# NJM2670.net
KiCad netlist of a schematic drawn in EAGLE
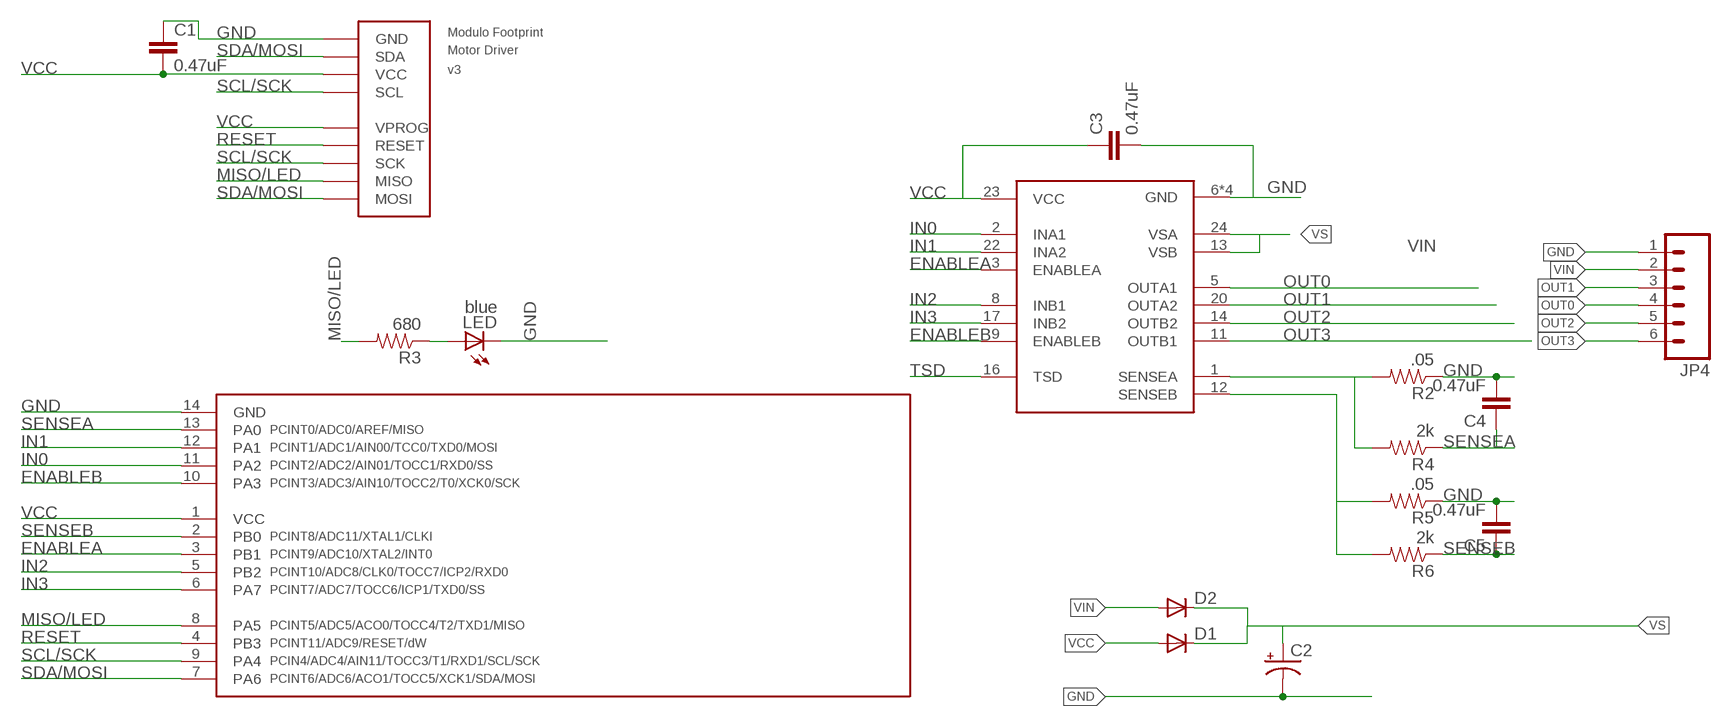
[diagram p0: schematic, sheet 1]

(export (version "E")
  (design (tool "Eeschema 10.0.6"))
  (components
    (comp (ref "C1")
      (value "0.47uF")
      (footprint "eagle-import:0805")
      (libsource (lib "eagle-import") (part "CAP0805"))
    )
    (comp (ref "C2")
      (value "CAP_POLC")
      (footprint "eagle-import:PANASONIC_C")
      (libsource (lib "eagle-import") (part "CAP_POLC"))
    )
    (comp (ref "C3")
      (value "0.47uF")
      (footprint "eagle-import:0805")
      (libsource (lib "eagle-import") (part "CAP0805"))
    )
    (comp (ref "C4")
      (value "0.47uF")
      (footprint "eagle-import:0805")
      (libsource (lib "eagle-import") (part "CAP0805"))
    )
    (comp (ref "C5")
      (value "0.47uF")
      (footprint "eagle-import:0805")
      (libsource (lib "eagle-import") (part "CAP0805"))
    )
    (comp (ref "D1")
      (value "DIODESMA")
      (footprint "eagle-import:SMA-DIODE")
      (libsource (lib "eagle-import") (part "DIODESMA"))
    )
    (comp (ref "D2")
      (value "DIODESMA")
      (footprint "eagle-import:SMA-DIODE")
      (libsource (lib "eagle-import") (part "DIODESMA"))
    )
    (comp (ref "JP4")
      (value "M063.5MM-6")
      (footprint "eagle-import:SCREWTERMINAL-3.5MM-6")
      (libsource (lib "eagle-import") (part "M063.5MM-6"))
    )
    (comp (ref "LED")
      (value "blue")
      (footprint "eagle-import:CHIPLED_0805")
      (libsource (lib "eagle-import") (part "LEDCHIPLED_0805"))
    )
    (comp (ref "R2")
      (value ".05")
      (footprint "eagle-import:0805")
      (libsource (lib "eagle-import") (part "RESISTOR0805-RES"))
    )
    (comp (ref "R3")
      (value "680")
      (footprint "eagle-import:0805")
      (libsource (lib "eagle-import") (part "RESISTOR0805-RES"))
    )
    (comp (ref "R4")
      (value "2k")
      (footprint "eagle-import:0805")
      (libsource (lib "eagle-import") (part "RESISTOR0805-RES"))
    )
    (comp (ref "R5")
      (value ".05")
      (footprint "eagle-import:0805")
      (libsource (lib "eagle-import") (part "RESISTOR0805-RES"))
    )
    (comp (ref "R6")
      (value "2k")
      (footprint "eagle-import:0805")
      (libsource (lib "eagle-import") (part "RESISTOR0805-RES"))
    )
    (comp (ref "U$1")
      (value "FOOTPRINTFOOTPRINT-2")
      (footprint "eagle-import:FOOTPRINT2")
      (fields (field (name "BOARD") "Motor Driver") (field (name "VERSION") "v3"))
      (libsource (lib "eagle-import") (part "FOOTPRINTFOOTPRINT-2"))
    )
    (comp (ref "U$3")
      (value "TINY841")
      (footprint "eagle-import:SOIC14")
      (libsource (lib "eagle-import") (part "TINY841"))
    )
    (comp (ref "U$6")
      (value "NJM2670")
      (footprint "eagle-import:SOP-24-E3")
      (libsource (lib "eagle-import") (part "NJM2670"))
    )
  )
  (nets
    (net (code "1") (name "/ENABLEA") (class "Default")
      (node (ref "U$3") (pin "3") (pinfunction "PB1_3") (pintype "bidirectional"))
      (node (ref "U$6") (pin "3") (pinfunction "ENABLEA_3") (pintype "bidirectional"))
    )
    (net (code "2") (name "/ENABLEB") (class "Default")
      (node (ref "U$3") (pin "10") (pinfunction "PA3_10") (pintype "bidirectional"))
      (node (ref "U$6") (pin "9") (pinfunction "ENABLEB_9") (pintype "bidirectional"))
    )
    (net (code "3") (name "/IN0") (class "Default")
      (node (ref "U$3") (pin "11") (pinfunction "PA2_11") (pintype "bidirectional"))
      (node (ref "U$6") (pin "2") (pinfunction "INA1_2") (pintype "bidirectional"))
    )
    (net (code "4") (name "/IN1") (class "Default")
      (node (ref "U$3") (pin "12") (pinfunction "PA1_12") (pintype "bidirectional"))
      (node (ref "U$6") (pin "22") (pinfunction "INA2_22") (pintype "bidirectional"))
    )
    (net (code "5") (name "/IN2") (class "Default")
      (node (ref "U$3") (pin "5") (pinfunction "PB2_5") (pintype "bidirectional"))
      (node (ref "U$6") (pin "8") (pinfunction "INB1_8") (pintype "bidirectional"))
    )
    (net (code "6") (name "/IN3") (class "Default")
      (node (ref "U$3") (pin "6") (pinfunction "PA7_6") (pintype "bidirectional"))
      (node (ref "U$6") (pin "17") (pinfunction "INB2_17") (pintype "bidirectional"))
    )
    (net (code "7") (name "/MISO{slash}LED") (class "Default")
      (node (ref "R3") (pin "2") (pinfunction "2_2") (pintype "passive"))
      (node (ref "U$1") (pin "PROG3") (pinfunction "MISO_PROG3") (pintype "bidirectional"))
      (node (ref "U$3") (pin "8") (pinfunction "PA5_8") (pintype "bidirectional"))
    )
    (net (code "8") (name "/RESET") (class "Default")
      (node (ref "U$1") (pin "PROG1") (pinfunction "RESET_PROG1") (pintype "bidirectional"))
      (node (ref "U$3") (pin "4") (pinfunction "PB3_4") (pintype "bidirectional"))
    )
    (net (code "9") (name "/SCL{slash}SCK") (class "Default")
      (node (ref "U$1") (pin "BUS3") (pinfunction "SCL_BUS3") (pintype "bidirectional"))
      (node (ref "U$1") (pin "PROG2") (pinfunction "SCK_PROG2") (pintype "bidirectional"))
      (node (ref "U$3") (pin "9") (pinfunction "PA4_9") (pintype "bidirectional"))
    )
    (net (code "10") (name "/SDA{slash}MOSI") (class "Default")
      (node (ref "U$1") (pin "BUS1") (pinfunction "SDA_BUS1") (pintype "bidirectional"))
      (node (ref "U$1") (pin "PROG4") (pinfunction "MOSI_PROG4") (pintype "bidirectional"))
      (node (ref "U$3") (pin "7") (pinfunction "PA6_7") (pintype "bidirectional"))
    )
    (net (code "11") (name "/SENSEA") (class "Default")
      (node (ref "C4") (pin "1") (pinfunction "1_1") (pintype "passive"))
      (node (ref "R4") (pin "1") (pinfunction "1_1") (pintype "passive"))
      (node (ref "U$3") (pin "13") (pinfunction "PA0_13") (pintype "bidirectional"))
    )
    (net (code "12") (name "/SENSEB") (class "Default")
      (node (ref "C5") (pin "1") (pinfunction "1_1") (pintype "passive"))
      (node (ref "R6") (pin "1") (pinfunction "1_1") (pintype "passive"))
      (node (ref "U$3") (pin "2") (pinfunction "PB0_2") (pintype "bidirectional"))
    )
    (net (code "13") (name "/TSD") (class "Default")
      (node (ref "U$6") (pin "16") (pinfunction "TSD_16") (pintype "bidirectional"))
    )
    (net (code "14") (name "GND") (class "Default")
      (node (ref "C1") (pin "1") (pinfunction "1_1") (pintype "passive"))
      (node (ref "C2") (pin "-") (pinfunction "-_-") (pintype "passive"))
      (node (ref "C3") (pin "2") (pinfunction "2_2") (pintype "passive"))
      (node (ref "C4") (pin "2") (pinfunction "2_2") (pintype "passive"))
      (node (ref "C5") (pin "2") (pinfunction "2_2") (pintype "passive"))
      (node (ref "JP4") (pin "1") (pinfunction "1_1") (pintype "passive"))
      (node (ref "LED") (pin "C") (pinfunction "C_C") (pintype "passive"))
      (node (ref "R2") (pin "1") (pinfunction "1_1") (pintype "passive"))
      (node (ref "R5") (pin "1") (pinfunction "1_1") (pintype "passive"))
      (node (ref "U$1") (pin "BUS0") (pinfunction "GND_BUS0") (pintype "bidirectional"))
      (node (ref "U$3") (pin "14") (pinfunction "GND_14") (pintype "bidirectional"))
      (node (ref "U$6") (pin "18") (pinfunction "GND_18") (pintype "bidirectional"))
      (node (ref "U$6") (pin "19") (pinfunction "GND_19") (pintype "bidirectional"))
      (node (ref "U$6") (pin "6") (pinfunction "GND_6") (pintype "bidirectional"))
      (node (ref "U$6") (pin "7") (pinfunction "GND_7") (pintype "bidirectional"))
    )
    (net (code "15") (name "Net-(LED-PadA)") (class "Default")
      (node (ref "LED") (pin "A") (pinfunction "A_A") (pintype "passive"))
      (node (ref "R3") (pin "1") (pinfunction "1_1") (pintype "passive"))
    )
    (net (code "16") (name "Net-(U$6-SENSEA)") (class "Default")
      (node (ref "R2") (pin "2") (pinfunction "2_2") (pintype "passive"))
      (node (ref "R4") (pin "2") (pinfunction "2_2") (pintype "passive"))
      (node (ref "U$6") (pin "1") (pinfunction "SENSEA_1") (pintype "bidirectional"))
    )
    (net (code "17") (name "Net-(U$6-SENSEB)") (class "Default")
      (node (ref "R5") (pin "2") (pinfunction "2_2") (pintype "passive"))
      (node (ref "R6") (pin "2") (pinfunction "2_2") (pintype "passive"))
      (node (ref "U$6") (pin "12") (pinfunction "SENSEB_12") (pintype "bidirectional"))
    )
    (net (code "18") (name "OUT0") (class "Default")
      (node (ref "JP4") (pin "4") (pinfunction "4_4") (pintype "passive"))
      (node (ref "U$6") (pin "5") (pinfunction "OUTA1_5") (pintype "bidirectional"))
    )
    (net (code "19") (name "OUT1") (class "Default")
      (node (ref "JP4") (pin "3") (pinfunction "3_3") (pintype "passive"))
      (node (ref "U$6") (pin "20") (pinfunction "OUTA2_20") (pintype "bidirectional"))
    )
    (net (code "20") (name "OUT2") (class "Default")
      (node (ref "JP4") (pin "5") (pinfunction "5_5") (pintype "passive"))
      (node (ref "U$6") (pin "14") (pinfunction "OUTB2_14") (pintype "bidirectional"))
    )
    (net (code "21") (name "OUT3") (class "Default")
      (node (ref "JP4") (pin "6") (pinfunction "6_6") (pintype "passive"))
      (node (ref "U$6") (pin "11") (pinfunction "OUTB1_11") (pintype "bidirectional"))
    )
    (net (code "22") (name "VCC") (class "Default")
      (node (ref "C1") (pin "2") (pinfunction "2_2") (pintype "passive"))
      (node (ref "C3") (pin "1") (pinfunction "1_1") (pintype "passive"))
      (node (ref "D1") (pin "A") (pinfunction "A_A") (pintype "passive"))
      (node (ref "U$1") (pin "BUS2") (pinfunction "VCC_BUS2") (pintype "bidirectional"))
      (node (ref "U$1") (pin "PROG0") (pinfunction "VPROG_PROG0") (pintype "bidirectional"))
      (node (ref "U$3") (pin "1") (pinfunction "VCC_1") (pintype "bidirectional"))
      (node (ref "U$6") (pin "23") (pinfunction "VCC_23") (pintype "bidirectional"))
    )
    (net (code "23") (name "VIN") (class "Default")
      (node (ref "D2") (pin "A") (pinfunction "A_A") (pintype "passive"))
      (node (ref "JP4") (pin "2") (pinfunction "2_2") (pintype "passive"))
    )
    (net (code "24") (name "VS") (class "Default")
      (node (ref "C2") (pin "+") (pinfunction "+_+") (pintype "passive"))
      (node (ref "D1") (pin "C") (pinfunction "C_C") (pintype "passive"))
      (node (ref "D2") (pin "C") (pinfunction "C_C") (pintype "passive"))
      (node (ref "U$6") (pin "13") (pinfunction "VSB_13") (pintype "bidirectional"))
      (node (ref "U$6") (pin "24") (pinfunction "VSA_24") (pintype "bidirectional"))
    )
  )
)
